# SCH_DITO2_2026-01-28.net
KiCad netlist of a schematic drawn in EasyEDA
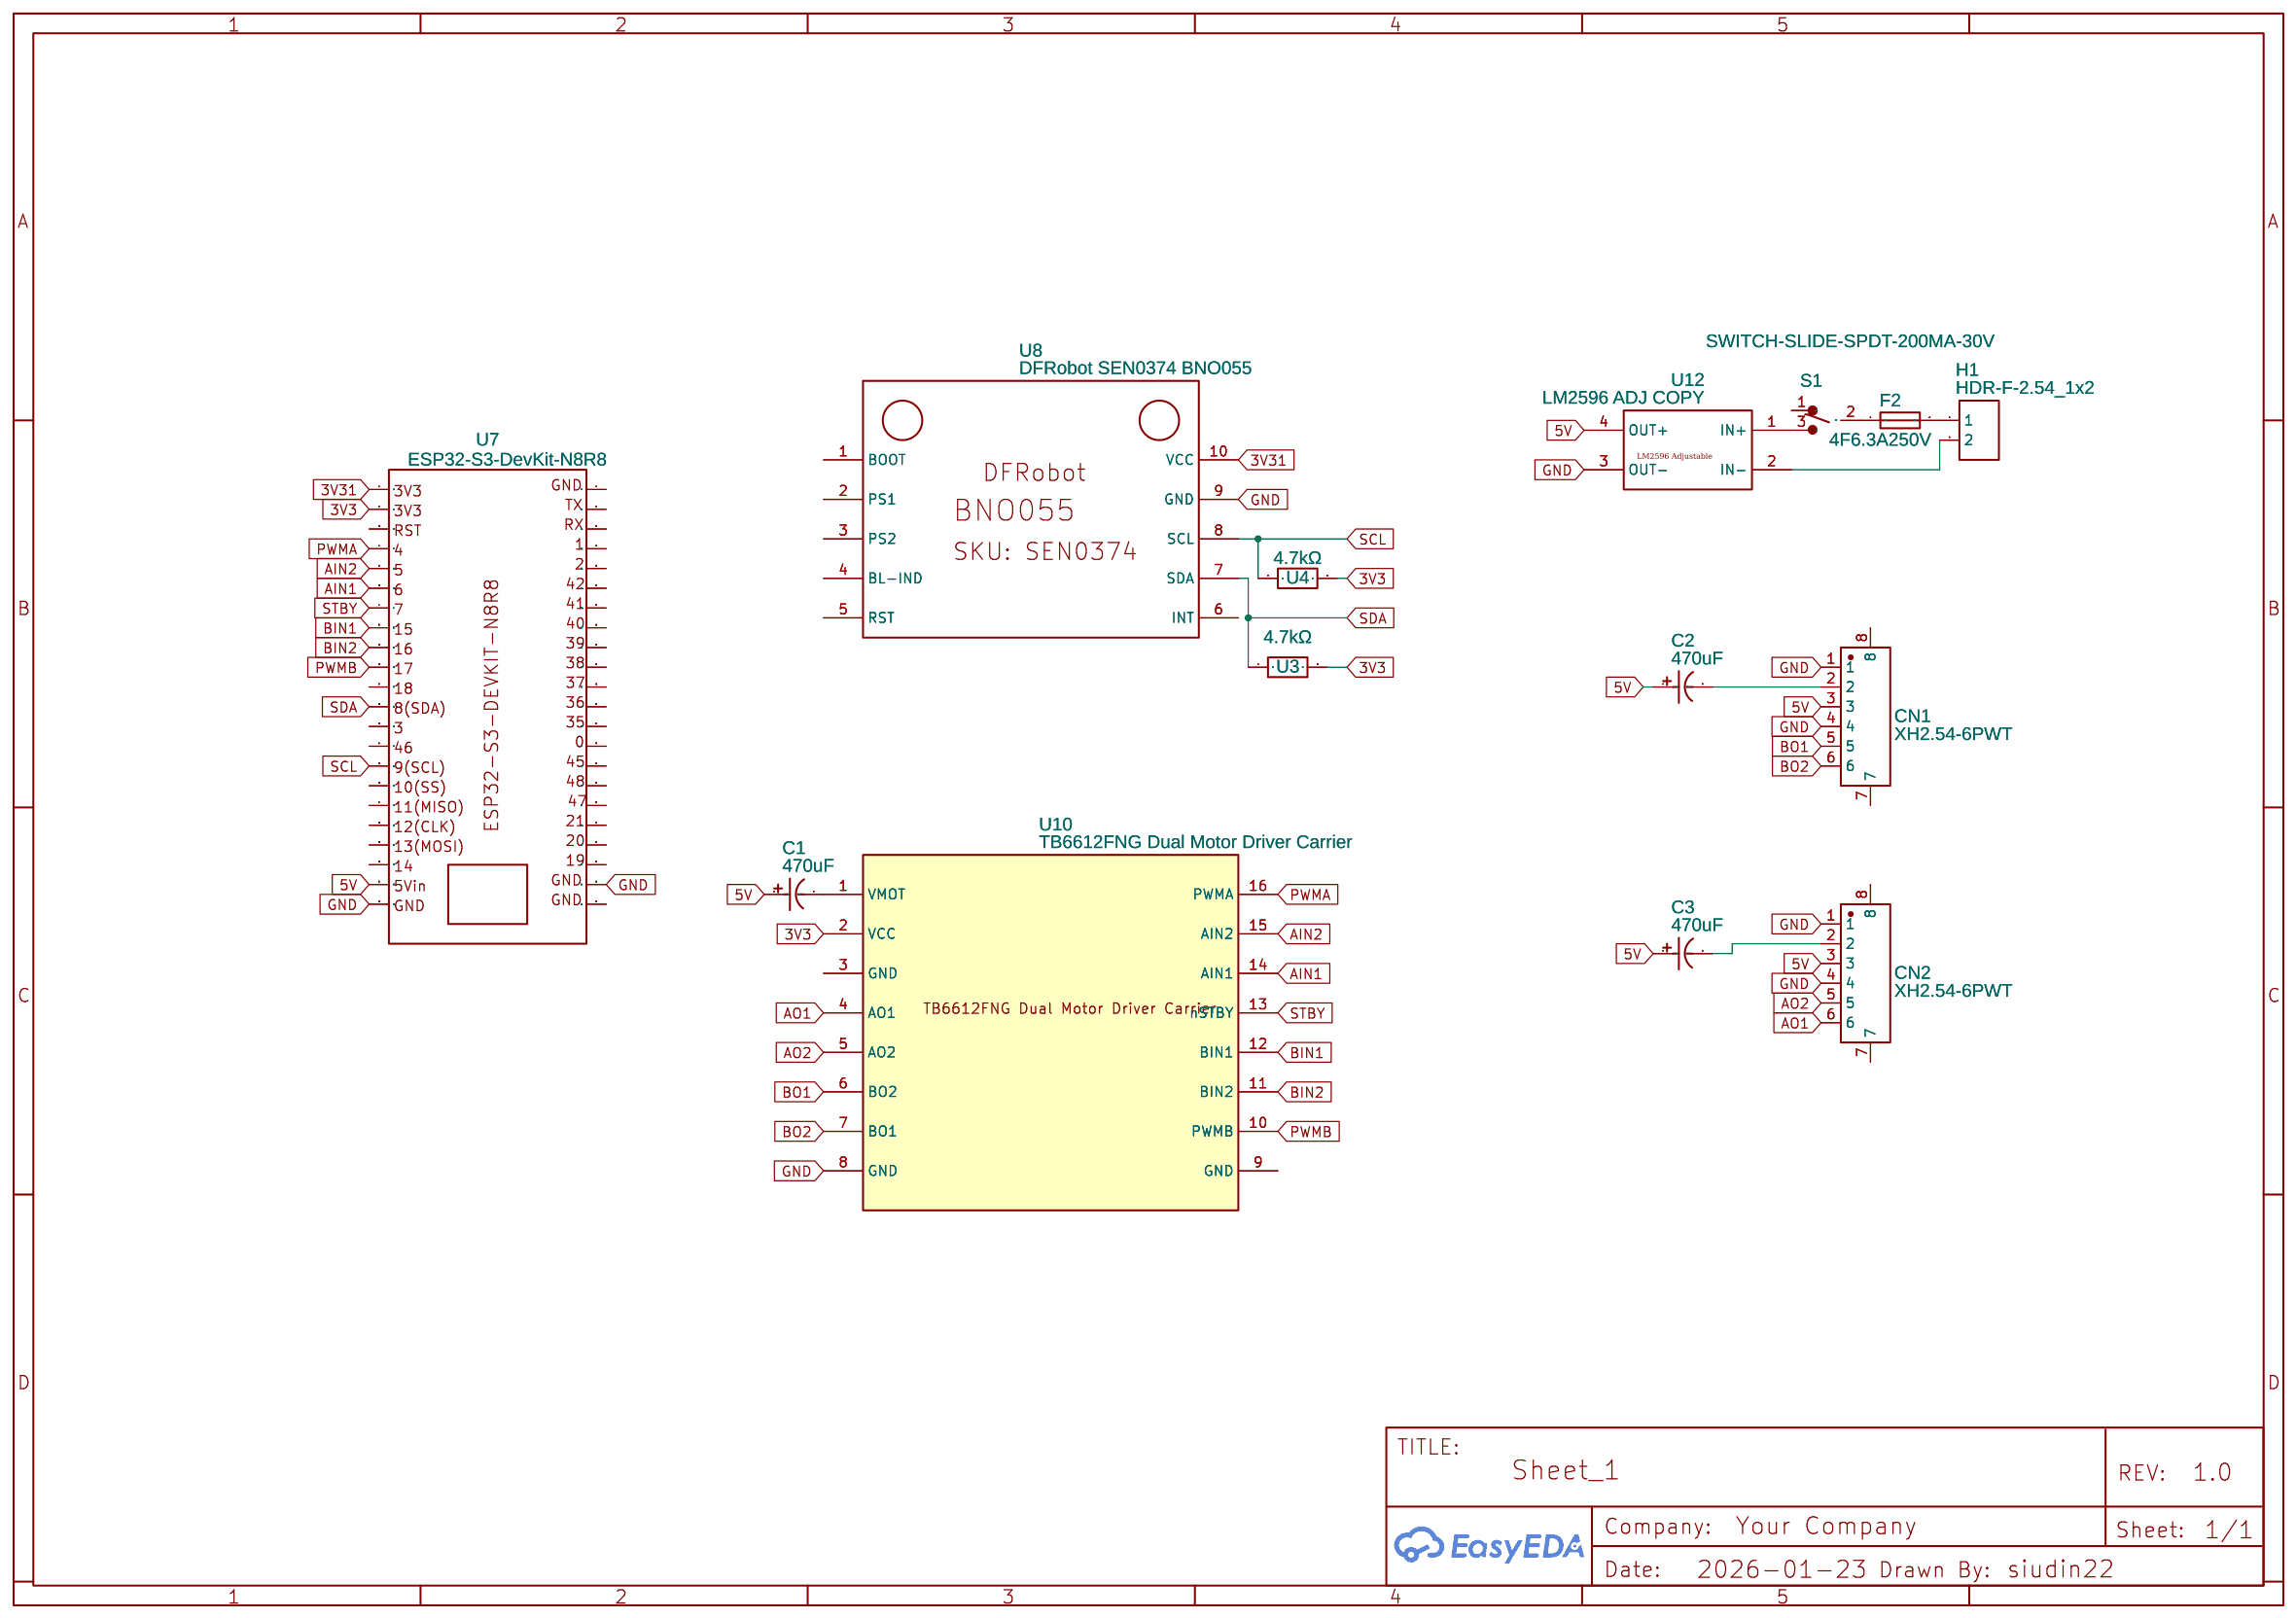
[diagram p0: schematic sheet]

(export (version "E")
  (design (tool "Eeschema 10.0.6"))
  (components
    (comp (ref "C1")
      (value "470uF")
      (fields (field (name "Manufacturer Part") "470uF 25V 8*14") (field (name "Manufacturer") "ValuePro"))
      (libsource (lib "") (part "470UF 25V 8X14"))
    )
    (comp (ref "C2")
      (value "470uF")
      (fields (field (name "Manufacturer Part") "470uF 25V 8*14") (field (name "Manufacturer") "ValuePro"))
      (libsource (lib "") (part "470UF 25V 8X14"))
    )
    (comp (ref "C3")
      (value "470uF")
      (fields (field (name "Manufacturer Part") "470uF 25V 8*14") (field (name "Manufacturer") "ValuePro"))
      (libsource (lib "") (part "470UF 25V 8X14"))
    )
    (comp (ref "CN1")
      (value "XH2.54-6PWT")
      (fields (field (name "Manufacturer") "XUNPU(讯普)"))
      (libsource (lib "") (part "XH2.54-6PWT"))
    )
    (comp (ref "CN2")
      (value "XH2.54-6PWT")
      (fields (field (name "Manufacturer") "XUNPU(讯普)"))
      (libsource (lib "") (part "XH2.54-6PWT"))
    )
    (comp (ref "F2")
      (value "4F6.3A250V")
      (fields (field (name "Manufacturer") "xcfuse(旭程)"))
      (libsource (lib "") (part "4F6.3A250V"))
    )
    (comp (ref "H1") (value "HDR-F-2.54_1x2") (libsource (lib "") (part "HDR-F-2.54_1x2")))
    (comp (ref "S1")
      (value "SWITCH-SLIDE-SPDT-200MA-30V")
      (libsource (lib "") (part "SWITCH-SLIDE-SPDT-200MA-30V"))
    )
    (comp (ref "U3")
      (value "4.7kΩ")
      (fields (field (name "Manufacturer Part") "B5J4K7E") (field (name "Manufacturer") "Ohmite"))
      (libsource (lib "") (part "B5J4K7E"))
    )
    (comp (ref "U4")
      (value "4.7kΩ")
      (fields (field (name "Manufacturer Part") "B5J4K7E") (field (name "Manufacturer") "Ohmite"))
      (libsource (lib "") (part "B5J4K7E"))
    )
    (comp (ref "U7")
      (value "ESP32-S3-DevKit-N8R8")
      (fields (field (name "Manufacturer") "WaveShare"))
      (libsource (lib "") (part "ESP32-S3-DevKit-N8R8"))
    )
    (comp (ref "U8") (value "DFRobot SEN0374 BNO055") (libsource (lib "") (part "DFRobot SEN0374 BNO055")))
    (comp (ref "U10")
      (value "TB6612FNG Dual Motor Driver Carrier")
      (libsource (lib "") (part "TB6612FNG Dual Motor Driver Carrier"))
    )
    (comp (ref "U12") (value "LM2596 ADJ COPY") (libsource (lib "") (part "BuckConverters_LM2596_Adj")))
  )
  (nets
    (net (code "1") (name "3V3") (class "Default")
      (node (ref "U10") (pin "2") (pinfunction "VCC_2") (pintype "unspecified"))
      (node (ref "U3") (pin "2") (pinfunction "2_2") (pintype "unspecified"))
      (node (ref "U4") (pin "2") (pinfunction "2_2") (pintype "unspecified"))
      (node (ref "U7") (pin "2") (pinfunction "2_2") (pintype "unspecified"))
    )
    (net (code "2") (name "3V31") (class "Default")
      (node (ref "U7") (pin "1") (pinfunction "1_1") (pintype "unspecified"))
      (node (ref "U8") (pin "10") (pinfunction "VCC_10") (pintype "unspecified"))
    )
    (net (code "3") (name "5V") (class "Default")
      (node (ref "C1") (pin "1") (pinfunction "1_1") (pintype "input"))
      (node (ref "C2") (pin "1") (pinfunction "1_1") (pintype "input"))
      (node (ref "C3") (pin "1") (pinfunction "1_1") (pintype "input"))
      (node (ref "CN1") (pin "3") (pinfunction "3_3") (pintype "unspecified"))
      (node (ref "CN2") (pin "3") (pinfunction "3_3") (pintype "unspecified"))
      (node (ref "U12") (pin "4") (pinfunction "OUT+_4") (pintype "unspecified"))
      (node (ref "U7") (pin "21") (pinfunction "21_21") (pintype "unspecified"))
    )
    (net (code "4") (name "AIN1") (class "Default")
      (node (ref "U10") (pin "14") (pinfunction "AIN1_14") (pintype "unspecified"))
      (node (ref "U7") (pin "6") (pinfunction "6_6") (pintype "unspecified"))
    )
    (net (code "5") (name "AIN2") (class "Default")
      (node (ref "U10") (pin "15") (pinfunction "AIN2_15") (pintype "unspecified"))
      (node (ref "U7") (pin "5") (pinfunction "5_5") (pintype "unspecified"))
    )
    (net (code "6") (name "AO1") (class "Default")
      (node (ref "CN2") (pin "6") (pinfunction "6_6") (pintype "unspecified"))
      (node (ref "U10") (pin "4") (pinfunction "AO1_4") (pintype "unspecified"))
    )
    (net (code "7") (name "AO2") (class "Default")
      (node (ref "CN2") (pin "5") (pinfunction "5_5") (pintype "unspecified"))
      (node (ref "U10") (pin "5") (pinfunction "AO2_5") (pintype "unspecified"))
    )
    (net (code "8") (name "BIN1") (class "Default")
      (node (ref "U10") (pin "12") (pinfunction "BIN1_12") (pintype "unspecified"))
      (node (ref "U7") (pin "8") (pinfunction "8_8") (pintype "unspecified"))
    )
    (net (code "9") (name "BIN2") (class "Default")
      (node (ref "U10") (pin "11") (pinfunction "BIN2_11") (pintype "unspecified"))
      (node (ref "U7") (pin "9") (pinfunction "9_9") (pintype "unspecified"))
    )
    (net (code "10") (name "BO1") (class "Default")
      (node (ref "CN1") (pin "5") (pinfunction "5_5") (pintype "unspecified"))
      (node (ref "U10") (pin "6") (pinfunction "BO2_6") (pintype "unspecified"))
    )
    (net (code "11") (name "BO2") (class "Default")
      (node (ref "CN1") (pin "6") (pinfunction "6_6") (pintype "unspecified"))
      (node (ref "U10") (pin "7") (pinfunction "BO1_7") (pintype "unspecified"))
    )
    (net (code "12") (name "GND") (class "Default")
      (node (ref "CN1") (pin "1") (pinfunction "1_1") (pintype "unspecified"))
      (node (ref "CN1") (pin "4") (pinfunction "4_4") (pintype "unspecified"))
      (node (ref "CN2") (pin "1") (pinfunction "1_1") (pintype "unspecified"))
      (node (ref "CN2") (pin "4") (pinfunction "4_4") (pintype "unspecified"))
      (node (ref "U10") (pin "8") (pinfunction "GND_8") (pintype "unspecified"))
      (node (ref "U12") (pin "3") (pinfunction "OUT-_3") (pintype "unspecified"))
      (node (ref "U7") (pin "22") (pinfunction "22_22") (pintype "unspecified"))
      (node (ref "U7") (pin "24") (pinfunction "24_24") (pintype "unspecified"))
      (node (ref "U8") (pin "9") (pinfunction "GND_9") (pintype "unspecified"))
    )
    (net (code "13") (name "Net-(C2-Pad2)") (class "Default")
      (node (ref "C2") (pin "2") (pinfunction "2_2") (pintype "input"))
      (node (ref "CN1") (pin "2") (pinfunction "2_2") (pintype "unspecified"))
    )
    (net (code "14") (name "Net-(C3-Pad2)") (class "Default")
      (node (ref "C3") (pin "2") (pinfunction "2_2") (pintype "input"))
      (node (ref "CN2") (pin "2") (pinfunction "2_2") (pintype "unspecified"))
    )
    (net (code "15") (name "Net-(F2-Pad1)") (class "Default")
      (node (ref "F2") (pin "1") (pinfunction "1_1") (pintype "unspecified"))
      (node (ref "S1") (pin "2") (pinfunction "2_2") (pintype "input"))
    )
    (net (code "16") (name "Net-(F2-Pad2)") (class "Default")
      (node (ref "F2") (pin "2") (pinfunction "2_2") (pintype "unspecified"))
      (node (ref "H1") (pin "1") (pinfunction "1_1") (pintype "input"))
    )
    (net (code "17") (name "Net-(U10-VMOT)") (class "Default")
      (node (ref "C1") (pin "2") (pinfunction "2_2") (pintype "input"))
      (node (ref "U10") (pin "1") (pinfunction "VMOT_1") (pintype "unspecified"))
    )
    (net (code "18") (name "Net-(U12-IN+)") (class "Default")
      (node (ref "S1") (pin "3") (pinfunction "3_3") (pintype "input"))
      (node (ref "U12") (pin "1") (pinfunction "IN+_1") (pintype "unspecified"))
    )
    (net (code "19") (name "Net-(U12-IN-)") (class "Default")
      (node (ref "H1") (pin "2") (pinfunction "2_2") (pintype "input"))
      (node (ref "U12") (pin "2") (pinfunction "IN-_2") (pintype "unspecified"))
    )
    (net (code "20") (name "PWMA") (class "Default")
      (node (ref "U10") (pin "16") (pinfunction "PWMA_16") (pintype "unspecified"))
      (node (ref "U7") (pin "4") (pinfunction "4_4") (pintype "unspecified"))
    )
    (net (code "21") (name "PWMB") (class "Default")
      (node (ref "U10") (pin "10") (pinfunction "PWMB_10") (pintype "unspecified"))
      (node (ref "U7") (pin "10") (pinfunction "10_10") (pintype "unspecified"))
    )
    (net (code "22") (name "SCL") (class "Default")
      (node (ref "U4") (pin "1") (pinfunction "1_1") (pintype "unspecified"))
      (node (ref "U7") (pin "15") (pinfunction "15_15") (pintype "unspecified"))
      (node (ref "U8") (pin "8") (pinfunction "SCL_8") (pintype "unspecified"))
    )
    (net (code "23") (name "SDA") (class "Default")
      (node (ref "U3") (pin "1") (pinfunction "1_1") (pintype "unspecified"))
      (node (ref "U7") (pin "12") (pinfunction "12_12") (pintype "unspecified"))
      (node (ref "U8") (pin "7") (pinfunction "SDA_7") (pintype "unspecified"))
    )
    (net (code "24") (name "STBY") (class "Default")
      (node (ref "U10") (pin "13") (pinfunction "nSTBY_13") (pintype "unspecified"))
      (node (ref "U7") (pin "7") (pinfunction "7_7") (pintype "unspecified"))
    )
    (net (code "25") (name "unconnected-(CN1-Pad7)") (class "Default")
      (node (ref "CN1") (pin "7") (pinfunction "7_7") (pintype "unspecified"))
    )
    (net (code "26") (name "unconnected-(CN1-Pad8)") (class "Default")
      (node (ref "CN1") (pin "8") (pinfunction "8_8") (pintype "unspecified"))
    )
    (net (code "27") (name "unconnected-(CN2-Pad7)") (class "Default")
      (node (ref "CN2") (pin "7") (pinfunction "7_7") (pintype "unspecified"))
    )
    (net (code "28") (name "unconnected-(CN2-Pad8)") (class "Default")
      (node (ref "CN2") (pin "8") (pinfunction "8_8") (pintype "unspecified"))
    )
    (net (code "29") (name "unconnected-(S1-Pad1)") (class "Default")
      (node (ref "S1") (pin "1") (pinfunction "1_1") (pintype "input"))
    )
    (net (code "30") (name "unconnected-(U7-Pad3)") (class "Default")
      (node (ref "U7") (pin "3") (pinfunction "3_3") (pintype "unspecified"))
    )
    (net (code "31") (name "unconnected-(U7-Pad11)") (class "Default")
      (node (ref "U7") (pin "11") (pinfunction "11_11") (pintype "unspecified"))
    )
    (net (code "32") (name "unconnected-(U7-Pad13)") (class "Default")
      (node (ref "U7") (pin "13") (pinfunction "13_13") (pintype "unspecified"))
    )
    (net (code "33") (name "unconnected-(U7-Pad14)") (class "Default")
      (node (ref "U7") (pin "14") (pinfunction "14_14") (pintype "unspecified"))
    )
    (net (code "34") (name "unconnected-(U7-Pad16)") (class "Default")
      (node (ref "U7") (pin "16") (pinfunction "16_16") (pintype "unspecified"))
    )
    (net (code "35") (name "unconnected-(U7-Pad17)") (class "Default")
      (node (ref "U7") (pin "17") (pinfunction "17_17") (pintype "unspecified"))
    )
    (net (code "36") (name "unconnected-(U7-Pad18)") (class "Default")
      (node (ref "U7") (pin "18") (pinfunction "18_18") (pintype "unspecified"))
    )
    (net (code "37") (name "unconnected-(U7-Pad19)") (class "Default")
      (node (ref "U7") (pin "19") (pinfunction "19_19") (pintype "unspecified"))
    )
    (net (code "38") (name "unconnected-(U7-Pad20)") (class "Default")
      (node (ref "U7") (pin "20") (pinfunction "20_20") (pintype "unspecified"))
    )
    (net (code "39") (name "unconnected-(U7-Pad23)") (class "Default")
      (node (ref "U7") (pin "23") (pinfunction "23_23") (pintype "unspecified"))
    )
    (net (code "40") (name "unconnected-(U7-Pad25)") (class "Default")
      (node (ref "U7") (pin "25") (pinfunction "25_25") (pintype "unspecified"))
    )
    (net (code "41") (name "unconnected-(U7-Pad26)") (class "Default")
      (node (ref "U7") (pin "26") (pinfunction "26_26") (pintype "unspecified"))
    )
    (net (code "42") (name "unconnected-(U7-Pad27)") (class "Default")
      (node (ref "U7") (pin "27") (pinfunction "27_27") (pintype "unspecified"))
    )
    (net (code "43") (name "unconnected-(U7-Pad28)") (class "Default")
      (node (ref "U7") (pin "28") (pinfunction "28_28") (pintype "unspecified"))
    )
    (net (code "44") (name "unconnected-(U7-Pad29)") (class "Default")
      (node (ref "U7") (pin "29") (pinfunction "29_29") (pintype "unspecified"))
    )
    (net (code "45") (name "unconnected-(U7-Pad30)") (class "Default")
      (node (ref "U7") (pin "30") (pinfunction "30_30") (pintype "unspecified"))
    )
    (net (code "46") (name "unconnected-(U7-Pad31)") (class "Default")
      (node (ref "U7") (pin "31") (pinfunction "31_31") (pintype "unspecified"))
    )
    (net (code "47") (name "unconnected-(U7-Pad32)") (class "Default")
      (node (ref "U7") (pin "32") (pinfunction "32_32") (pintype "unspecified"))
    )
    (net (code "48") (name "unconnected-(U7-Pad33)") (class "Default")
      (node (ref "U7") (pin "33") (pinfunction "33_33") (pintype "unspecified"))
    )
    (net (code "49") (name "unconnected-(U7-Pad34)") (class "Default")
      (node (ref "U7") (pin "34") (pinfunction "34_34") (pintype "unspecified"))
    )
    (net (code "50") (name "unconnected-(U7-Pad35)") (class "Default")
      (node (ref "U7") (pin "35") (pinfunction "35_35") (pintype "unspecified"))
    )
    (net (code "51") (name "unconnected-(U7-Pad36)") (class "Default")
      (node (ref "U7") (pin "36") (pinfunction "36_36") (pintype "unspecified"))
    )
    (net (code "52") (name "unconnected-(U7-Pad37)") (class "Default")
      (node (ref "U7") (pin "37") (pinfunction "37_37") (pintype "unspecified"))
    )
    (net (code "53") (name "unconnected-(U7-Pad38)") (class "Default")
      (node (ref "U7") (pin "38") (pinfunction "38_38") (pintype "unspecified"))
    )
    (net (code "54") (name "unconnected-(U7-Pad39)") (class "Default")
      (node (ref "U7") (pin "39") (pinfunction "39_39") (pintype "unspecified"))
    )
    (net (code "55") (name "unconnected-(U7-Pad40)") (class "Default")
      (node (ref "U7") (pin "40") (pinfunction "40_40") (pintype "unspecified"))
    )
    (net (code "56") (name "unconnected-(U7-Pad41)") (class "Default")
      (node (ref "U7") (pin "41") (pinfunction "41_41") (pintype "unspecified"))
    )
    (net (code "57") (name "unconnected-(U7-Pad42)") (class "Default")
      (node (ref "U7") (pin "42") (pinfunction "42_42") (pintype "unspecified"))
    )
    (net (code "58") (name "unconnected-(U7-Pad43)") (class "Default")
      (node (ref "U7") (pin "43") (pinfunction "43_43") (pintype "unspecified"))
    )
    (net (code "59") (name "unconnected-(U7-Pad44)") (class "Default")
      (node (ref "U7") (pin "44") (pinfunction "44_44") (pintype "unspecified"))
    )
    (net (code "60") (name "unconnected-(U8-BL-IND-Pad4)") (class "Default")
      (node (ref "U8") (pin "4") (pinfunction "BL-IND_4") (pintype "unspecified"))
    )
    (net (code "61") (name "unconnected-(U8-BOOT-Pad1)") (class "Default")
      (node (ref "U8") (pin "1") (pinfunction "BOOT_1") (pintype "unspecified"))
    )
    (net (code "62") (name "unconnected-(U8-INT-Pad6)") (class "Default")
      (node (ref "U8") (pin "6") (pinfunction "INT_6") (pintype "unspecified"))
    )
    (net (code "63") (name "unconnected-(U8-PS1-Pad2)") (class "Default")
      (node (ref "U8") (pin "2") (pinfunction "PS1_2") (pintype "unspecified"))
    )
    (net (code "64") (name "unconnected-(U8-PS2-Pad3)") (class "Default")
      (node (ref "U8") (pin "3") (pinfunction "PS2_3") (pintype "unspecified"))
    )
    (net (code "65") (name "unconnected-(U8-RST-Pad5)") (class "Default")
      (node (ref "U8") (pin "5") (pinfunction "RST_5") (pintype "unspecified"))
    )
    (net (code "66") (name "unconnected-(U10-GND-Pad3)") (class "Default")
      (node (ref "U10") (pin "3") (pinfunction "GND_3") (pintype "unspecified"))
    )
    (net (code "67") (name "unconnected-(U10-GND-Pad9)") (class "Default")
      (node (ref "U10") (pin "9") (pinfunction "GND_9") (pintype "unspecified"))
    )
  )
)
